# Tonegenerator.net
KiCad netlist of a schematic drawn in Altium Designer
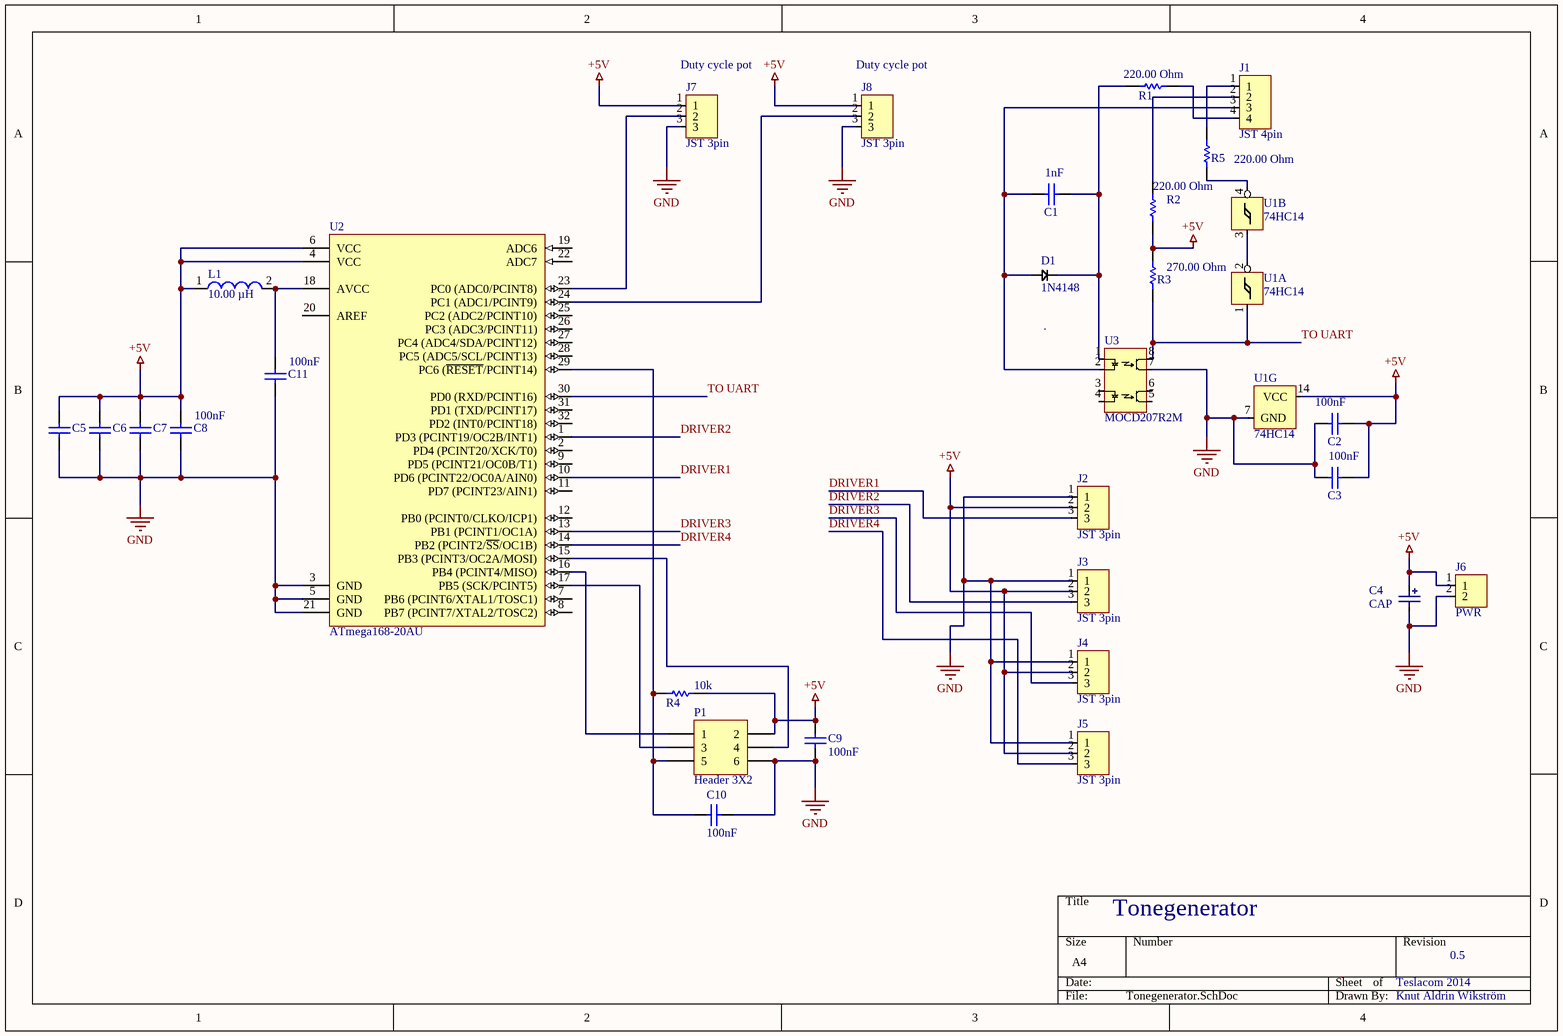
[diagram p0: Tonegenerator.SchDoc]

(export (version "E")
  (design (tool "Eeschema 10.0.6"))
  (components
    (comp (ref "C1")
      (value "1nF")
      (footprint "CAPC0805(2012)100_L")
      (description "CAP 1nF 50V ±5% 0805 (2012 Metric) Thickness 1mm SMD")
      (fields (field (name "TOLERANCE") "±5%") (field (name "Comment") "CAP 1nF 50V 0805(2012)"))
      (libsource (lib "Altium Content Vault") (part "CMP-1036-02977-1"))
    )
    (comp (ref "C2")
      (value "100nF")
      (footprint "CAPC0805(2012)100_L")
      (description "CAP 100nF 50V ±5% 0805 (2012 Metric) Thickness 1mm SMD")
      (fields (field (name "TOLERANCE") "±5%") (field (name "Comment") "CAP 100nF 50V 0805(2012)"))
      (libsource (lib "Altium Content Vault") (part "CMP-1036-04418-1"))
    )
    (comp (ref "C3")
      (value "100nF")
      (footprint "CAPC0805(2012)100_L")
      (description "CAP 100nF 50V ±5% 0805 (2012 Metric) Thickness 1mm SMD")
      (fields (field (name "TOLERANCE") "±5%") (field (name "Comment") "CAP 100nF 50V 0805(2012)"))
      (libsource (lib "Altium Content Vault") (part "CMP-1036-04418-1"))
    )
    (comp (ref "C4") (value "CAP") (footprint "CAP 2.5mm") (libsource (lib "Schlib1") (part "CAP")))
    (comp (ref "C5")
      (value "CAP 100nF 50V 0805(2012)")
      (footprint "CAPC0805(2012)100_L")
      (description "CAP 100nF 50V ±5% 0805 (2012 Metric) Thickness 1mm SMD")
      (fields (field (name "TOLERANCE") "±5%"))
      (libsource (lib "Altium Content Vault") (part "CAP"))
    )
    (comp (ref "C6")
      (value "CAP 100nF 50V 0805(2012)")
      (footprint "CAPC0805(2012)100_L")
      (description "CAP 100nF 50V ±5% 0805 (2012 Metric) Thickness 1mm SMD")
      (fields (field (name "TOLERANCE") "±5%"))
      (libsource (lib "Altium Content Vault") (part "CAP"))
    )
    (comp (ref "C7")
      (value "CAP 100nF 50V 0805(2012)")
      (footprint "CAPC0805(2012)100_L")
      (description "CAP 100nF 50V ±5% 0805 (2012 Metric) Thickness 1mm SMD")
      (fields (field (name "TOLERANCE") "±5%"))
      (libsource (lib "Altium Content Vault") (part "CAP"))
    )
    (comp (ref "C8")
      (value "100nF")
      (footprint "CAPC0805(2012)100_L")
      (description "CAP 100nF 50V ±5% 0805 (2012 Metric) Thickness 1mm SMD")
      (fields (field (name "TOLERANCE") "±5%") (field (name "Comment") "CAP 100nF 50V 0805(2012)"))
      (libsource (lib "Altium Content Vault") (part "CMP-1036-04418-1"))
    )
    (comp (ref "C9")
      (value "100nF")
      (footprint "CAPC0805(2012)100_L")
      (description "CAP 100nF 50V ±5% 0805 (2012 Metric) Thickness 1mm SMD")
      (fields (field (name "TOLERANCE") "±5%"))
      (libsource (lib "Altium Content Vault") (part "CMP-1036-04418-1"))
    )
    (comp (ref "C10")
      (value "100nF")
      (footprint "CAPC0805(2012)100_L")
      (description "CAP 100nF 50V ±5% 0805 (2012 Metric) Thickness 1mm SMD")
      (fields (field (name "TOLERANCE") "±5%"))
      (libsource (lib "Altium Content Vault") (part "CMP-1036-04418-1"))
    )
    (comp (ref "C11")
      (value "100nF")
      (footprint "CAPC0805(2012)100_L")
      (description "CAP 100nF 50V ±5% 0805 (2012 Metric) Thickness 1mm SMD")
      (fields (field (name "TOLERANCE") "±5%") (field (name "Comment") "CAP 100nF 50V 0805(2012)"))
      (libsource (lib "Altium Content Vault") (part "CMP-1036-04418-1"))
    )
    (comp (ref "D1") (value "1N4148") (footprint "1N4148") (libsource (lib "Schlib1") (part "1N4148")))
    (comp (ref "J1") (value "JST 4pin") (footprint "JST 4pin") (libsource (lib "Schlib1") (part "JST 4pin")))
    (comp (ref "J2") (value "JST 3pin") (footprint "JST 3pin") (libsource (lib "Schlib1") (part "JST 3pin")))
    (comp (ref "J3") (value "JST 3pin") (footprint "JST 3pin") (libsource (lib "Schlib1") (part "JST 3pin")))
    (comp (ref "J4") (value "JST 3pin") (footprint "JST 3pin") (libsource (lib "Schlib1") (part "JST 3pin")))
    (comp (ref "J5") (value "JST 3pin") (footprint "JST 3pin") (libsource (lib "Schlib1") (part "JST 3pin")))
    (comp (ref "J6") (value "PWR") (footprint "JST 2pin") (libsource (lib "Schlib1") (part "JST 2pin")))
    (comp (ref "J7") (value "JST 3pin") (footprint "JST 3pin") (libsource (lib "Schlib1") (part "JST 3pin")))
    (comp (ref "J8") (value "JST 3pin") (footprint "JST 3pin") (libsource (lib "Schlib1") (part "JST 3pin")))
    (comp (ref "L1")
      (value "7447918")
      (footprint "SMD-1210")
      (description "SMD-Multilayer Inductor WE-MI, L = 10.00 µH")
      (fields (field (name "INDUCTANCE") "10.00 µH"))
      (libsource (lib "Altium Content Vault") (part "CMP-0221-00030-1"))
    )
    (comp (ref "P1")
      (value "Header 3X2")
      (footprint "HDR2X3")
      (description "Header, 3-Pin, Dual row")
      (fields (field (name "PUBLISHER") "Altium Limited"))
      (libsource (lib "Miscellaneous Connectors") (part "Header 3X2"))
    )
    (comp (ref "R1")
      (value "220.00 Ohm")
      (footprint "RESC0805(2012)_L")
      (description "220R 0.125W 5% 0805 (2012 Metric)  SMD")
      (fields (field (name "POWER") "0.125 W") (field (name "TOLERANCE") "5 %"))
      (libsource (lib "Altium Content Vault") (part "CMP-1013-00058-1"))
    )
    (comp (ref "R2")
      (value "220.00 Ohm")
      (footprint "RESC0805(2012)_L")
      (description "220R 0.125W 5% 0805 (2012 Metric)  SMD")
      (fields (field (name "POWER") "0.125 W") (field (name "TOLERANCE") "5 %"))
      (libsource (lib "Altium Content Vault") (part "CMP-1013-00058-1"))
    )
    (comp (ref "R3")
      (value "270.00 Ohm")
      (footprint "RESC0805(2012)_N")
      (description "270R 0.125W 5% 0805 (2012 Metric)  SMD")
      (fields (field (name "POWER") "0.125 W") (field (name "TOLERANCE") "5 %"))
      (libsource (lib "Altium Content Vault") (part "CMP-1013-00060-1"))
    )
    (comp (ref "R4")
      (value "10K 1% 0805(2012)")
      (footprint "RESC0805(2012)_M")
      (description "10K 0.125W 1% 0805 (2012 Metric)  SMD")
      (fields
        (field (name "TOLERANCE") "1 %")
        (field (name "POWER") "0.125 W")
        (field (name "READABLE VALUE") "10k")
      )
      (libsource (lib "Altium Content Vault") (part "CMP-1013-00623-1"))
    )
    (comp (ref "R5")
      (value "220.00 Ohm")
      (footprint "RESC0805(2012)_L")
      (description "220R 0.125W 5% 0805 (2012 Metric)  SMD")
      (fields (field (name "POWER") "0.125 W") (field (name "TOLERANCE") "5 %"))
      (libsource (lib "Altium Content Vault") (part "CMP-1013-00058-1"))
    )
    (comp (ref "U1") (value "74HC14") (footprint "SOP14") (libsource (lib "Schlib1") (part "74HC14")))
    (comp (ref "U2")
      (value "ATmega168-20AU")
      (footprint "32A_N")
      (libsource (lib "Altium Content Vault") (part "CMP-0095-00552-1"))
    )
    (comp (ref "U3") (value "MOCD207R2M") (footprint "SOP8") (libsource (lib "Schlib1") (part "MOCD207R2M")))
  )
  (nets
    (net (code "1") (name "+5V") (class "Default")
      (node (ref "C2") (pin "2") (pinfunction "2_2") (pintype "passive"))
      (node (ref "C3") (pin "2") (pinfunction "2_2") (pintype "passive"))
      (node (ref "C4") (pin "2") (pinfunction "2_2") (pintype "passive"))
      (node (ref "C5") (pin "2") (pinfunction "2_2") (pintype "passive"))
      (node (ref "C6") (pin "2") (pinfunction "2_2") (pintype "passive"))
      (node (ref "C7") (pin "2") (pinfunction "2_2") (pintype "passive"))
      (node (ref "C8") (pin "2") (pinfunction "2_2") (pintype "passive"))
      (node (ref "C9") (pin "2") (pinfunction "2_2") (pintype "passive"))
      (node (ref "J2") (pin "2") (pinfunction "2_2") (pintype "passive"))
      (node (ref "J3") (pin "2") (pinfunction "2_2") (pintype "passive"))
      (node (ref "J4") (pin "2") (pinfunction "2_2") (pintype "passive"))
      (node (ref "J5") (pin "2") (pinfunction "2_2") (pintype "passive"))
      (node (ref "J6") (pin "1") (pinfunction "1_1") (pintype "passive"))
      (node (ref "J7") (pin "1") (pinfunction "1_1") (pintype "passive"))
      (node (ref "J8") (pin "1") (pinfunction "1_1") (pintype "passive"))
      (node (ref "L1") (pin "1") (pinfunction "1_1") (pintype "passive"))
      (node (ref "P1") (pin "2") (pinfunction "2_2") (pintype "passive"))
      (node (ref "R2") (pin "1") (pinfunction "1_1") (pintype "passive"))
      (node (ref "R3") (pin "2") (pinfunction "2_2") (pintype "passive"))
      (node (ref "R4") (pin "2") (pinfunction "2_2") (pintype "passive"))
      (node (ref "U1") (pin "14") (pinfunction "VCC_14") (pintype "passive"))
      (node (ref "U2") (pin "4") (pinfunction "VCC_4") (pintype "power_in"))
      (node (ref "U2") (pin "6") (pinfunction "VCC_6") (pintype "power_in"))
    )
    (net (code "2") (name "/DRIVER1") (class "Default")
      (node (ref "J2") (pin "3") (pinfunction "3_3") (pintype "passive"))
      (node (ref "U2") (pin "10") (pinfunction "PD6_(PCINT22/OC0A/AIN0)_10") (pintype "bidirectional"))
    )
    (net (code "3") (name "/DRIVER2") (class "Default")
      (node (ref "J3") (pin "3") (pinfunction "3_3") (pintype "passive"))
      (node (ref "U2") (pin "1") (pinfunction "PD3_(PCINT19/OC2B/INT1)_1") (pintype "bidirectional"))
    )
    (net (code "4") (name "/DRIVER3") (class "Default")
      (node (ref "J4") (pin "3") (pinfunction "3_3") (pintype "passive"))
      (node (ref "U2") (pin "13") (pinfunction "PB1_(PCINT1/OC1A)_13") (pintype "bidirectional"))
    )
    (net (code "5") (name "/DRIVER4") (class "Default")
      (node (ref "J5") (pin "3") (pinfunction "3_3") (pintype "passive"))
      (node (ref "U2") (pin "14") (pinfunction "PB2_(PCINT2/~{SS}/OC1B)_14") (pintype "bidirectional"))
    )
    (net (code "6") (name "/TO UART") (class "Default")
      (node (ref "R3") (pin "1") (pinfunction "1_1") (pintype "passive"))
      (node (ref "U1") (pin "1") (pinfunction "1_1") (pintype "passive"))
      (node (ref "U2") (pin "30") (pinfunction "PD0_(RXD/PCINT16)_30") (pintype "bidirectional"))
      (node (ref "U3") (pin "8") (pinfunction "8_8") (pintype "passive"))
    )
    (net (code "7") (name "GND") (class "Default")
      (node (ref "C10") (pin "1") (pinfunction "1_1") (pintype "passive"))
      (node (ref "C11") (pin "1") (pinfunction "1_1") (pintype "passive"))
      (node (ref "C2") (pin "1") (pinfunction "1_1") (pintype "passive"))
      (node (ref "C3") (pin "1") (pinfunction "1_1") (pintype "passive"))
      (node (ref "C4") (pin "1") (pinfunction "1_1") (pintype "passive"))
      (node (ref "C5") (pin "1") (pinfunction "1_1") (pintype "passive"))
      (node (ref "C6") (pin "1") (pinfunction "1_1") (pintype "passive"))
      (node (ref "C7") (pin "1") (pinfunction "1_1") (pintype "passive"))
      (node (ref "C8") (pin "1") (pinfunction "1_1") (pintype "passive"))
      (node (ref "C9") (pin "1") (pinfunction "1_1") (pintype "passive"))
      (node (ref "J2") (pin "1") (pinfunction "1_1") (pintype "passive"))
      (node (ref "J3") (pin "1") (pinfunction "1_1") (pintype "passive"))
      (node (ref "J4") (pin "1") (pinfunction "1_1") (pintype "passive"))
      (node (ref "J5") (pin "1") (pinfunction "1_1") (pintype "passive"))
      (node (ref "J6") (pin "2") (pinfunction "2_2") (pintype "passive"))
      (node (ref "J7") (pin "3") (pinfunction "3_3") (pintype "passive"))
      (node (ref "J8") (pin "3") (pinfunction "3_3") (pintype "passive"))
      (node (ref "P1") (pin "6") (pinfunction "6_6") (pintype "passive"))
      (node (ref "U1") (pin "7") (pinfunction "GND_7") (pintype "passive"))
      (node (ref "U2") (pin "21") (pinfunction "GND_21") (pintype "power_in"))
      (node (ref "U2") (pin "3") (pinfunction "GND_3") (pintype "power_in"))
      (node (ref "U2") (pin "5") (pinfunction "GND_5") (pintype "power_in"))
      (node (ref "U3") (pin "7") (pinfunction "7_7") (pintype "passive"))
    )
    (net (code "8") (name "Net-(C1-Pad1)") (class "Default")
      (node (ref "C1") (pin "1") (pinfunction "1_1") (pintype "passive"))
      (node (ref "D1") (pin "A") (pinfunction "A_A") (pintype "passive"))
      (node (ref "J1") (pin "3") (pinfunction "3_3") (pintype "passive"))
      (node (ref "U3") (pin "2") (pinfunction "2_2") (pintype "passive"))
    )
    (net (code "9") (name "Net-(C1-Pad2)") (class "Default")
      (node (ref "C1") (pin "2") (pinfunction "2_2") (pintype "passive"))
      (node (ref "D1") (pin "K") (pinfunction "K_K") (pintype "passive"))
      (node (ref "R1") (pin "1") (pinfunction "1_1") (pintype "passive"))
      (node (ref "U3") (pin "1") (pinfunction "1_1") (pintype "passive"))
    )
    (net (code "10") (name "Net-(J1-Pad1)") (class "Default")
      (node (ref "J1") (pin "1") (pinfunction "1_1") (pintype "passive"))
      (node (ref "R5") (pin "2") (pinfunction "2_2") (pintype "passive"))
    )
    (net (code "11") (name "Net-(J1-Pad2)") (class "Default")
      (node (ref "J1") (pin "2") (pinfunction "2_2") (pintype "passive"))
      (node (ref "R2") (pin "2") (pinfunction "2_2") (pintype "passive"))
    )
    (net (code "12") (name "Net-(J1-Pad4)") (class "Default")
      (node (ref "J1") (pin "4") (pinfunction "4_4") (pintype "passive"))
      (node (ref "R1") (pin "2") (pinfunction "2_2") (pintype "passive"))
    )
    (net (code "13") (name "Net-(R5-Pad1)") (class "Default")
      (node (ref "R5") (pin "1") (pinfunction "1_1") (pintype "passive"))
      (node (ref "U1") (pin "4") (pinfunction "4_4") (pintype "passive"))
    )
    (net (code "14") (name "Net-(U1-Pad2)") (class "Default")
      (node (ref "U1") (pin "2") (pinfunction "2_2") (pintype "passive"))
      (node (ref "U1") (pin "3") (pinfunction "3_3") (pintype "passive"))
    )
    (net (code "15") (name "Net-(U2-AVCC)") (class "Default")
      (node (ref "C11") (pin "2") (pinfunction "2_2") (pintype "passive"))
      (node (ref "L1") (pin "2") (pinfunction "2_2") (pintype "passive"))
      (node (ref "U2") (pin "18") (pinfunction "AVCC_18") (pintype "power_in"))
    )
    (net (code "16") (name "Net-(U2-PB3_(PCINT3{slash}OC2A{slash}MOSI))") (class "Default")
      (node (ref "P1") (pin "4") (pinfunction "4_4") (pintype "passive"))
      (node (ref "U2") (pin "15") (pinfunction "PB3_(PCINT3/OC2A/MOSI)_15") (pintype "bidirectional"))
    )
    (net (code "17") (name "Net-(U2-PB4_(PCINT4{slash}MISO))") (class "Default")
      (node (ref "P1") (pin "1") (pinfunction "1_1") (pintype "passive"))
      (node (ref "U2") (pin "16") (pinfunction "PB4_(PCINT4/MISO)_16") (pintype "bidirectional"))
    )
    (net (code "18") (name "Net-(U2-PB5_(SCK{slash}PCINT5))") (class "Default")
      (node (ref "P1") (pin "3") (pinfunction "3_3") (pintype "passive"))
      (node (ref "U2") (pin "17") (pinfunction "PB5_(SCK/PCINT5)_17") (pintype "bidirectional"))
    )
    (net (code "19") (name "Net-(U2-PC0_(ADC0{slash}PCINT8))") (class "Default")
      (node (ref "J7") (pin "2") (pinfunction "2_2") (pintype "passive"))
      (node (ref "U2") (pin "23") (pinfunction "PC0_(ADC0/PCINT8)_23") (pintype "bidirectional"))
    )
    (net (code "20") (name "Net-(U2-PC1_(ADC1{slash}PCINT9))") (class "Default")
      (node (ref "J8") (pin "2") (pinfunction "2_2") (pintype "passive"))
      (node (ref "U2") (pin "24") (pinfunction "PC1_(ADC1/PCINT9)_24") (pintype "bidirectional"))
    )
    (net (code "21") (name "Net-(U2-PC6_(~{RESET}{slash}PCINT14))") (class "Default")
      (node (ref "C10") (pin "2") (pinfunction "2_2") (pintype "passive"))
      (node (ref "P1") (pin "5") (pinfunction "5_5") (pintype "passive"))
      (node (ref "R4") (pin "1") (pinfunction "1_1") (pintype "passive"))
      (node (ref "U2") (pin "29") (pinfunction "PC6_(~{RESET}/PCINT14)_29") (pintype "bidirectional"))
    )
    (net (code "22") (name "unconnected-(U2-ADC6-Pad19)") (class "Default")
      (node (ref "U2") (pin "19") (pinfunction "ADC6_19") (pintype "input"))
    )
    (net (code "23") (name "unconnected-(U2-ADC7-Pad22)") (class "Default")
      (node (ref "U2") (pin "22") (pinfunction "ADC7_22") (pintype "input"))
    )
    (net (code "24") (name "unconnected-(U2-AREF-Pad20)") (class "Default")
      (node (ref "U2") (pin "20") (pinfunction "AREF_20") (pintype "passive"))
    )
    (net (code "25") (name "unconnected-(U2-PB0_(PCINT0{slash}CLKO{slash}ICP1)-Pad12)") (class "Default")
      (node (ref "U2") (pin "12") (pinfunction "PB0_(PCINT0/CLKO/ICP1)_12") (pintype "bidirectional"))
    )
    (net (code "26") (name "unconnected-(U2-PB6_(PCINT6{slash}XTAL1{slash}TOSC1)-Pad7)") (class "Default")
      (node (ref "U2") (pin "7") (pinfunction "PB6_(PCINT6/XTAL1/TOSC1)_7") (pintype "bidirectional"))
    )
    (net (code "27") (name "unconnected-(U2-PB7_(PCINT7{slash}XTAL2{slash}TOSC2)-Pad8)") (class "Default")
      (node (ref "U2") (pin "8") (pinfunction "PB7_(PCINT7/XTAL2/TOSC2)_8") (pintype "bidirectional"))
    )
    (net (code "28") (name "unconnected-(U2-PC2_(ADC2{slash}PCINT10)-Pad25)") (class "Default")
      (node (ref "U2") (pin "25") (pinfunction "PC2_(ADC2/PCINT10)_25") (pintype "bidirectional"))
    )
    (net (code "29") (name "unconnected-(U2-PC3_(ADC3{slash}PCINT11)-Pad26)") (class "Default")
      (node (ref "U2") (pin "26") (pinfunction "PC3_(ADC3/PCINT11)_26") (pintype "bidirectional"))
    )
    (net (code "30") (name "unconnected-(U2-PC4_(ADC4{slash}SDA{slash}PCINT12)-Pad27)") (class "Default")
      (node (ref "U2") (pin "27") (pinfunction "PC4_(ADC4/SDA/PCINT12)_27") (pintype "bidirectional"))
    )
    (net (code "31") (name "unconnected-(U2-PC5_(ADC5{slash}SCL{slash}PCINT13)-Pad28)") (class "Default")
      (node (ref "U2") (pin "28") (pinfunction "PC5_(ADC5/SCL/PCINT13)_28") (pintype "bidirectional"))
    )
    (net (code "32") (name "unconnected-(U2-PD1_(TXD{slash}PCINT17)-Pad31)") (class "Default")
      (node (ref "U2") (pin "31") (pinfunction "PD1_(TXD/PCINT17)_31") (pintype "bidirectional"))
    )
    (net (code "33") (name "unconnected-(U2-PD2_(INT0{slash}PCINT18)-Pad32)") (class "Default")
      (node (ref "U2") (pin "32") (pinfunction "PD2_(INT0/PCINT18)_32") (pintype "bidirectional"))
    )
    (net (code "34") (name "unconnected-(U2-PD4_(PCINT20{slash}XCK{slash}T0)-Pad2)") (class "Default")
      (node (ref "U2") (pin "2") (pinfunction "PD4_(PCINT20/XCK/T0)_2") (pintype "bidirectional"))
    )
    (net (code "35") (name "unconnected-(U2-PD5_(PCINT21{slash}OC0B{slash}T1)-Pad9)") (class "Default")
      (node (ref "U2") (pin "9") (pinfunction "PD5_(PCINT21/OC0B/T1)_9") (pintype "bidirectional"))
    )
    (net (code "36") (name "unconnected-(U2-PD7_(PCINT23{slash}AIN1)-Pad11)") (class "Default")
      (node (ref "U2") (pin "11") (pinfunction "PD7_(PCINT23/AIN1)_11") (pintype "bidirectional"))
    )
    (net (code "37") (name "unconnected-(U3-Pad3)") (class "Default")
      (node (ref "U3") (pin "3") (pinfunction "3_3") (pintype "passive"))
    )
    (net (code "38") (name "unconnected-(U3-Pad4)") (class "Default")
      (node (ref "U3") (pin "4") (pinfunction "4_4") (pintype "passive"))
    )
    (net (code "39") (name "unconnected-(U3-Pad5)") (class "Default")
      (node (ref "U3") (pin "5") (pinfunction "5_5") (pintype "passive"))
    )
    (net (code "40") (name "unconnected-(U3-Pad6)") (class "Default")
      (node (ref "U3") (pin "6") (pinfunction "6_6") (pintype "passive"))
    )
  )
)
